# R2P_XXX_module.net
KiCad netlist of a schematic drawn in EAGLE
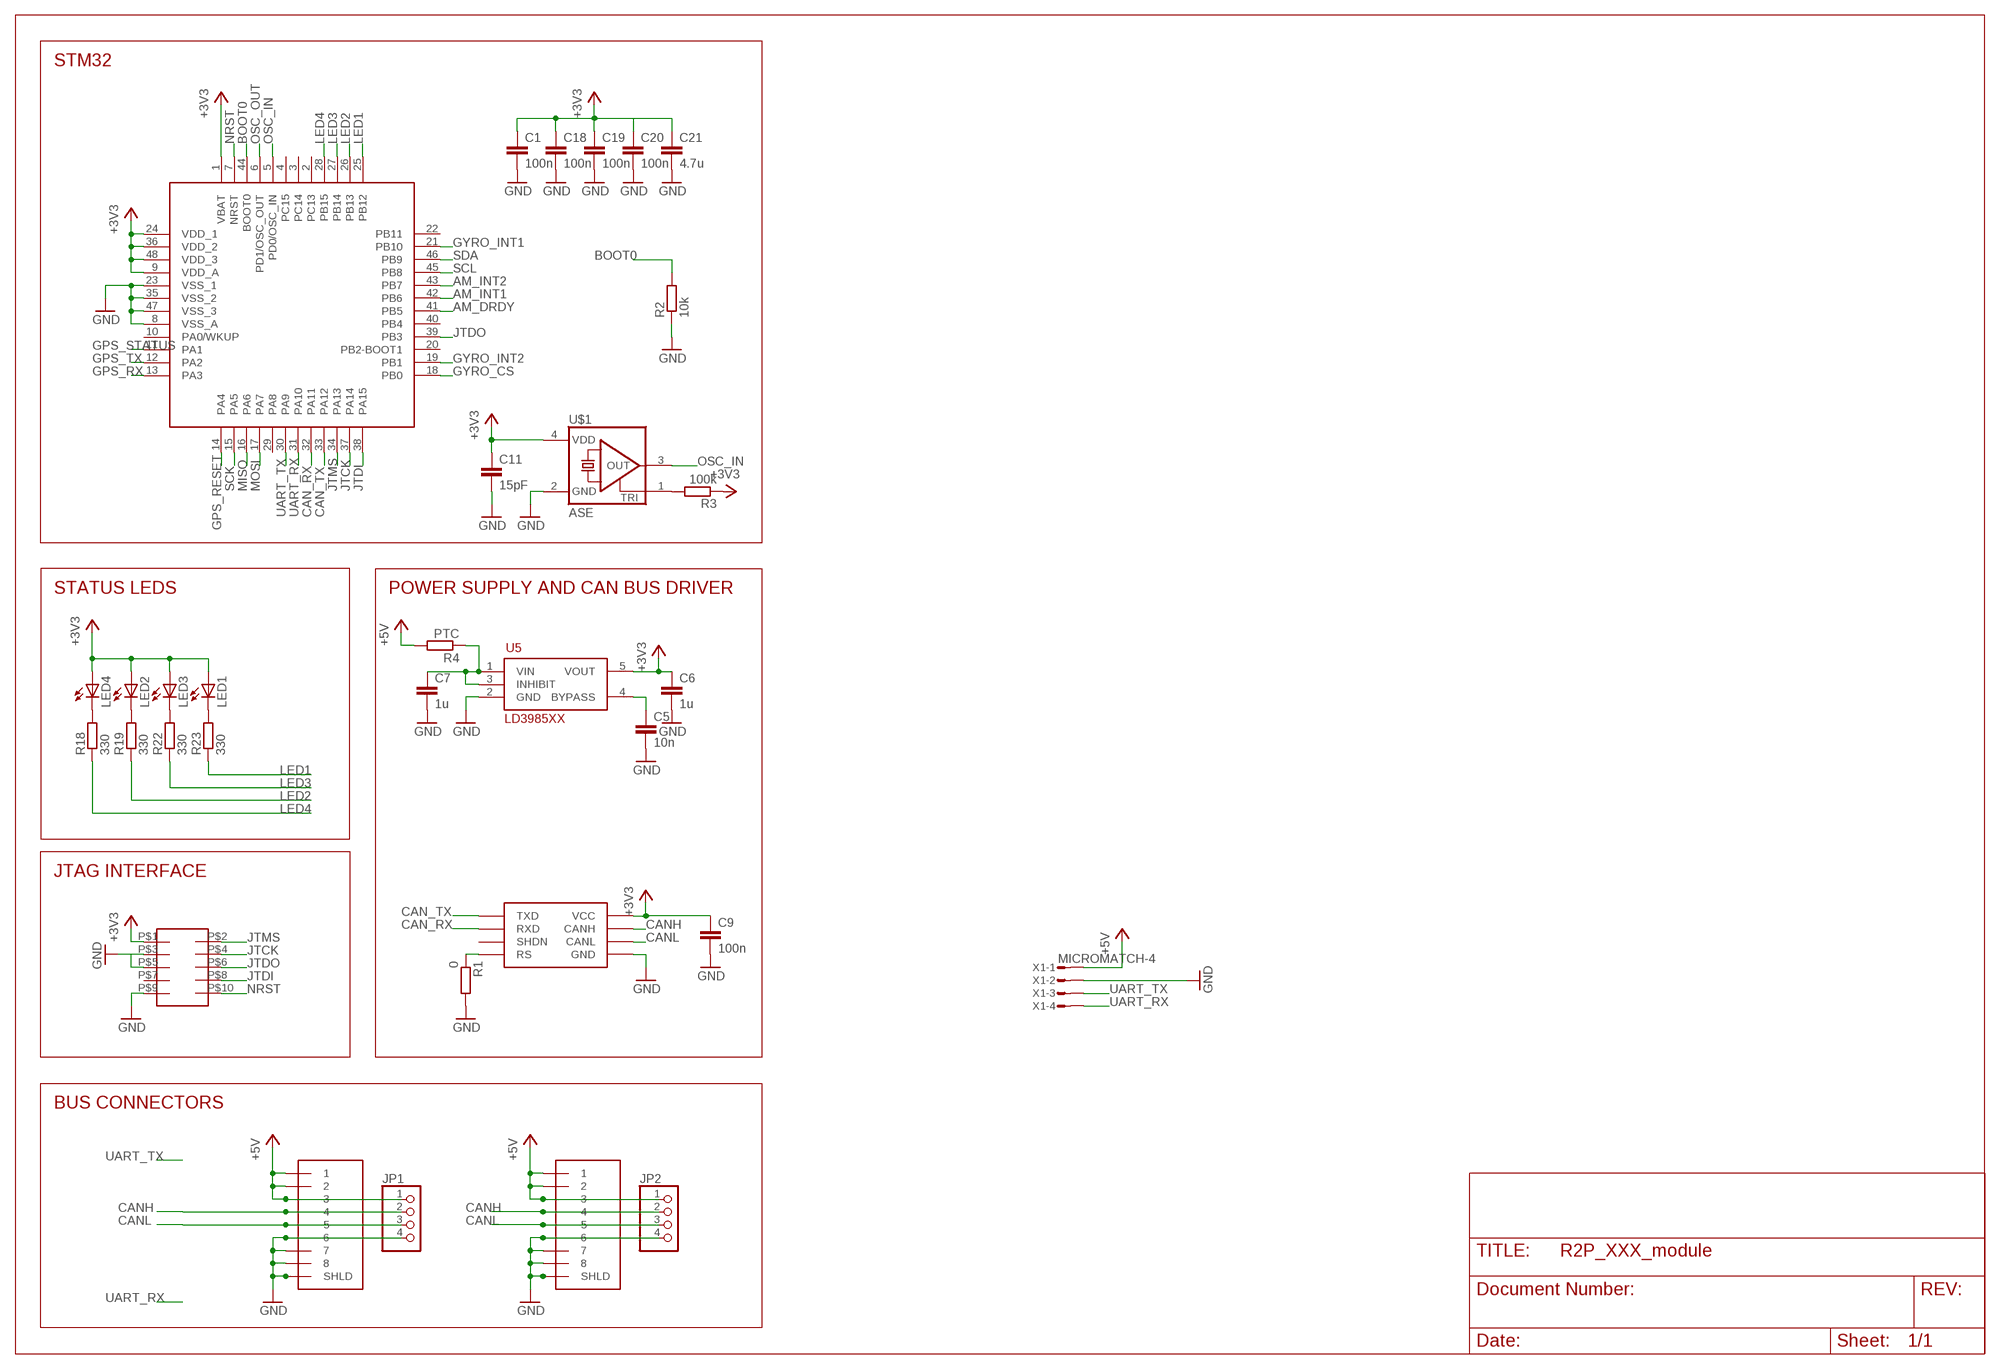
[diagram p0: schematic, sheet 1]

(export (version "E")
  (design (tool "Eeschema 10.0.6"))
  (components
    (comp (ref "1")
      (value "RJ45-43860")
      (footprint "eagle-import:0438600010")
      (libsource (lib "eagle-import") (part "RJ45-43860"))
    )
    (comp (ref "2")
      (value "RJ45-43860")
      (footprint "eagle-import:0438600010")
      (libsource (lib "eagle-import") (part "RJ45-43860"))
    )
    (comp (ref "C1")
      (value "100n")
      (footprint "eagle-import:C0603")
      (libsource (lib "eagle-import") (part "C-EUC0603"))
    )
    (comp (ref "C5")
      (value "10n")
      (footprint "eagle-import:C0603")
      (libsource (lib "eagle-import") (part "C-EUC0603"))
    )
    (comp (ref "C6")
      (value "1u")
      (footprint "eagle-import:C0603")
      (libsource (lib "eagle-import") (part "C-EUC0603"))
    )
    (comp (ref "C7")
      (value "1u")
      (footprint "eagle-import:C0603")
      (libsource (lib "eagle-import") (part "C-EUC0603"))
    )
    (comp (ref "C9")
      (value "100n")
      (footprint "eagle-import:C0603")
      (libsource (lib "eagle-import") (part "C-EUC0603"))
    )
    (comp (ref "C11")
      (value "15pF")
      (footprint "eagle-import:C0603")
      (libsource (lib "eagle-import") (part "C-EUC0603"))
    )
    (comp (ref "C18")
      (value "100n")
      (footprint "eagle-import:C0603")
      (libsource (lib "eagle-import") (part "C-EUC0603"))
    )
    (comp (ref "C19")
      (value "100n")
      (footprint "eagle-import:C0603")
      (libsource (lib "eagle-import") (part "C-EUC0603"))
    )
    (comp (ref "C20")
      (value "100n")
      (footprint "eagle-import:C0603")
      (libsource (lib "eagle-import") (part "C-EUC0603"))
    )
    (comp (ref "C21")
      (value "4.7u")
      (footprint "eagle-import:C0805")
      (libsource (lib "eagle-import") (part "C-EUC0805"))
    )
    (comp (ref "JP1")
      (value "PINHD-1X4")
      (footprint "eagle-import:1X04")
      (libsource (lib "eagle-import") (part "PINHD-1X4"))
    )
    (comp (ref "JP2")
      (value "PINHD-1X4")
      (footprint "eagle-import:1X04")
      (libsource (lib "eagle-import") (part "PINHD-1X4"))
    )
    (comp (ref "LED1")
      (value "LEDCHIPLED_0805")
      (footprint "eagle-import:CHIPLED_0805")
      (libsource (lib "eagle-import") (part "LEDCHIPLED_0805"))
    )
    (comp (ref "LED2")
      (value "LEDCHIPLED_0805")
      (footprint "eagle-import:CHIPLED_0805")
      (libsource (lib "eagle-import") (part "LEDCHIPLED_0805"))
    )
    (comp (ref "LED3")
      (value "LEDCHIPLED_0805")
      (footprint "eagle-import:CHIPLED_0805")
      (libsource (lib "eagle-import") (part "LEDCHIPLED_0805"))
    )
    (comp (ref "LED4")
      (value "LEDCHIPLED_0805")
      (footprint "eagle-import:CHIPLED_0805")
      (libsource (lib "eagle-import") (part "LEDCHIPLED_0805"))
    )
    (comp (ref "R1")
      (value "0")
      (footprint "eagle-import:R0603")
      (libsource (lib "eagle-import") (part "R-EU_R0603"))
    )
    (comp (ref "R2")
      (value "10k")
      (footprint "eagle-import:R0603")
      (libsource (lib "eagle-import") (part "R-EU_R0603"))
    )
    (comp (ref "R3")
      (value "100k")
      (footprint "eagle-import:R0603")
      (libsource (lib "eagle-import") (part "R-EU_R0603"))
    )
    (comp (ref "R4")
      (value "PTC")
      (footprint "eagle-import:R0603")
      (libsource (lib "eagle-import") (part "R-EU_R0603"))
    )
    (comp (ref "R18")
      (value "330")
      (footprint "eagle-import:R0603")
      (libsource (lib "eagle-import") (part "R-EU_R0603"))
    )
    (comp (ref "R19")
      (value "330")
      (footprint "eagle-import:R0603")
      (libsource (lib "eagle-import") (part "R-EU_R0603"))
    )
    (comp (ref "R22")
      (value "330")
      (footprint "eagle-import:R0603")
      (libsource (lib "eagle-import") (part "R-EU_R0603"))
    )
    (comp (ref "R23")
      (value "330")
      (footprint "eagle-import:R0603")
      (libsource (lib "eagle-import") (part "R-EU_R0603"))
    )
    (comp (ref "SOT1")
      (value "MAX3051")
      (footprint "eagle-import:SOT23-8L")
      (libsource (lib "eagle-import") (part "MAX3051"))
    )
    (comp (ref "U$1")
      (value "ASE")
      (footprint "eagle-import:ASE")
      (libsource (lib "eagle-import") (part "ASE"))
    )
    (comp (ref "U$4")
      (value "FTSH-105")
      (footprint "eagle-import:FTSH-105")
      (libsource (lib "eagle-import") (part "FTSH-105"))
    )
    (comp (ref "U1")
      (value "STM32F103CX")
      (footprint "eagle-import:LQFP48")
      (libsource (lib "eagle-import") (part "STM32F103CX"))
    )
    (comp (ref "U5")
      (value "LD3985XX")
      (footprint "eagle-import:SOT23-5L")
      (libsource (lib "eagle-import") (part "LD3985XX"))
    )
    (comp (ref "X1")
      (value "MICROMATCH-4")
      (footprint "eagle-import:MICROMATCH-4")
      (libsource (lib "eagle-import") (part "MICROMATCH-4"))
    )
  )
  (nets
    (net (code "1") (name "+3V3") (class "Default")
      (node (ref "C1") (pin "1") (pinfunction "1_1") (pintype "passive"))
      (node (ref "C11") (pin "1") (pinfunction "1_1") (pintype "passive"))
      (node (ref "C18") (pin "1") (pinfunction "1_1") (pintype "passive"))
      (node (ref "C19") (pin "1") (pinfunction "1_1") (pintype "passive"))
      (node (ref "C20") (pin "1") (pinfunction "1_1") (pintype "passive"))
      (node (ref "C21") (pin "1") (pinfunction "1_1") (pintype "passive"))
      (node (ref "C6") (pin "1") (pinfunction "1_1") (pintype "passive"))
      (node (ref "C9") (pin "1") (pinfunction "1_1") (pintype "passive"))
      (node (ref "LED1") (pin "A") (pinfunction "A_A") (pintype "passive"))
      (node (ref "LED2") (pin "A") (pinfunction "A_A") (pintype "passive"))
      (node (ref "LED3") (pin "A") (pinfunction "A_A") (pintype "passive"))
      (node (ref "LED4") (pin "A") (pinfunction "A_A") (pintype "passive"))
      (node (ref "R3") (pin "1") (pinfunction "1_1") (pintype "passive"))
      (node (ref "SOT1") (pin "P$3") (pinfunction "VCC_P$3") (pintype "bidirectional"))
      (node (ref "U$1") (pin "4") (pinfunction "VDD_4") (pintype "power_in"))
      (node (ref "U$4") (pin "P$1") (pinfunction "P$1_P$1") (pintype "bidirectional"))
      (node (ref "U1") (pin "1") (pinfunction "VBAT_1") (pintype "bidirectional"))
      (node (ref "U1") (pin "24") (pinfunction "VDD_1_24") (pintype "bidirectional"))
      (node (ref "U1") (pin "36") (pinfunction "VDD_2_36") (pintype "bidirectional"))
      (node (ref "U1") (pin "48") (pinfunction "VDD_3_48") (pintype "bidirectional"))
      (node (ref "U1") (pin "9") (pinfunction "VDD_A_9") (pintype "bidirectional"))
      (node (ref "U5") (pin "5") (pinfunction "VOUT_5") (pintype "bidirectional"))
    )
    (net (code "2") (name "+5V") (class "Default")
      (node (ref "1") (pin "P$1") (pinfunction "1_P$1") (pintype "bidirectional"))
      (node (ref "1") (pin "P$2") (pinfunction "2_P$2") (pintype "bidirectional"))
      (node (ref "1") (pin "P$3") (pinfunction "3_P$3") (pintype "bidirectional"))
      (node (ref "2") (pin "P$1") (pinfunction "1_P$1") (pintype "bidirectional"))
      (node (ref "2") (pin "P$2") (pinfunction "2_P$2") (pintype "bidirectional"))
      (node (ref "2") (pin "P$3") (pinfunction "3_P$3") (pintype "bidirectional"))
      (node (ref "JP1") (pin "1") (pinfunction "1_1") (pintype "passive"))
      (node (ref "JP2") (pin "1") (pinfunction "1_1") (pintype "passive"))
      (node (ref "R4") (pin "2") (pinfunction "2_2") (pintype "passive"))
      (node (ref "X1") (pin "1") (pinfunction "S_1") (pintype "passive"))
    )
    (net (code "3") (name "/AM_DRDY") (class "Default")
      (node (ref "U1") (pin "41") (pinfunction "PB5_41") (pintype "bidirectional"))
    )
    (net (code "4") (name "/AM_INT1") (class "Default")
      (node (ref "U1") (pin "42") (pinfunction "PB6_42") (pintype "bidirectional"))
    )
    (net (code "5") (name "/AM_INT2") (class "Default")
      (node (ref "U1") (pin "43") (pinfunction "PB7_43") (pintype "bidirectional"))
    )
    (net (code "6") (name "/BOOT0") (class "Default")
      (node (ref "R2") (pin "2") (pinfunction "2_2") (pintype "passive"))
      (node (ref "U1") (pin "44") (pinfunction "BOOT0_44") (pintype "bidirectional"))
    )
    (net (code "7") (name "/CANH") (class "Default")
      (node (ref "1") (pin "P$4") (pinfunction "4_P$4") (pintype "bidirectional"))
      (node (ref "2") (pin "P$4") (pinfunction "4_P$4") (pintype "bidirectional"))
      (node (ref "JP1") (pin "2") (pinfunction "2_2") (pintype "passive"))
      (node (ref "JP2") (pin "2") (pinfunction "2_2") (pintype "passive"))
      (node (ref "SOT1") (pin "P$7") (pinfunction "CANH_P$7") (pintype "bidirectional"))
    )
    (net (code "8") (name "/CANL") (class "Default")
      (node (ref "1") (pin "P$5") (pinfunction "5_P$5") (pintype "bidirectional"))
      (node (ref "2") (pin "P$5") (pinfunction "5_P$5") (pintype "bidirectional"))
      (node (ref "JP1") (pin "3") (pinfunction "3_3") (pintype "passive"))
      (node (ref "JP2") (pin "3") (pinfunction "3_3") (pintype "passive"))
      (node (ref "SOT1") (pin "P$6") (pinfunction "CANL_P$6") (pintype "bidirectional"))
    )
    (net (code "9") (name "/CAN_RX") (class "Default")
      (node (ref "SOT1") (pin "P$4") (pinfunction "RXD_P$4") (pintype "bidirectional"))
      (node (ref "U1") (pin "32") (pinfunction "PA11_32") (pintype "bidirectional"))
    )
    (net (code "10") (name "/CAN_TX") (class "Default")
      (node (ref "SOT1") (pin "P$1") (pinfunction "TXD_P$1") (pintype "bidirectional"))
      (node (ref "U1") (pin "33") (pinfunction "PA12_33") (pintype "bidirectional"))
    )
    (net (code "11") (name "/GPS_RESET") (class "Default")
      (node (ref "U1") (pin "14") (pinfunction "PA4_14") (pintype "bidirectional"))
    )
    (net (code "12") (name "/GPS_RX") (class "Default")
      (node (ref "U1") (pin "13") (pinfunction "PA3_13") (pintype "bidirectional"))
    )
    (net (code "13") (name "/GPS_STATUS") (class "Default")
      (node (ref "U1") (pin "11") (pinfunction "PA1_11") (pintype "bidirectional"))
    )
    (net (code "14") (name "/GPS_TX") (class "Default")
      (node (ref "U1") (pin "12") (pinfunction "PA2_12") (pintype "bidirectional"))
    )
    (net (code "15") (name "/GYRO_CS") (class "Default")
      (node (ref "U1") (pin "18") (pinfunction "PB0_18") (pintype "bidirectional"))
    )
    (net (code "16") (name "/GYRO_INT1") (class "Default")
      (node (ref "U1") (pin "21") (pinfunction "PB10_21") (pintype "bidirectional"))
    )
    (net (code "17") (name "/GYRO_INT2") (class "Default")
      (node (ref "U1") (pin "19") (pinfunction "PB1_19") (pintype "bidirectional"))
    )
    (net (code "18") (name "/JTCK") (class "Default")
      (node (ref "U$4") (pin "P$4") (pinfunction "P$4_P$4") (pintype "bidirectional"))
      (node (ref "U1") (pin "37") (pinfunction "PA14_37") (pintype "bidirectional"))
    )
    (net (code "19") (name "/JTDI") (class "Default")
      (node (ref "U$4") (pin "P$8") (pinfunction "P$8_P$8") (pintype "bidirectional"))
      (node (ref "U1") (pin "38") (pinfunction "PA15_38") (pintype "bidirectional"))
    )
    (net (code "20") (name "/JTDO") (class "Default")
      (node (ref "U$4") (pin "P$6") (pinfunction "P$6_P$6") (pintype "bidirectional"))
      (node (ref "U1") (pin "39") (pinfunction "PB3_39") (pintype "bidirectional"))
    )
    (net (code "21") (name "/JTMS") (class "Default")
      (node (ref "U$4") (pin "P$2") (pinfunction "P$2_P$2") (pintype "bidirectional"))
      (node (ref "U1") (pin "34") (pinfunction "PA13_34") (pintype "bidirectional"))
    )
    (net (code "22") (name "/LED1") (class "Default")
      (node (ref "R23") (pin "1") (pinfunction "1_1") (pintype "passive"))
      (node (ref "U1") (pin "25") (pinfunction "PB12_25") (pintype "bidirectional"))
    )
    (net (code "23") (name "/LED2") (class "Default")
      (node (ref "R19") (pin "1") (pinfunction "1_1") (pintype "passive"))
      (node (ref "U1") (pin "26") (pinfunction "PB13_26") (pintype "bidirectional"))
    )
    (net (code "24") (name "/LED3") (class "Default")
      (node (ref "R22") (pin "1") (pinfunction "1_1") (pintype "passive"))
      (node (ref "U1") (pin "27") (pinfunction "PB14_27") (pintype "bidirectional"))
    )
    (net (code "25") (name "/LED4") (class "Default")
      (node (ref "R18") (pin "1") (pinfunction "1_1") (pintype "passive"))
      (node (ref "U1") (pin "28") (pinfunction "PB15_28") (pintype "bidirectional"))
    )
    (net (code "26") (name "/MISO") (class "Default")
      (node (ref "U1") (pin "16") (pinfunction "PA6_16") (pintype "bidirectional"))
    )
    (net (code "27") (name "/MOSI") (class "Default")
      (node (ref "U1") (pin "17") (pinfunction "PA7_17") (pintype "bidirectional"))
    )
    (net (code "28") (name "/NRST") (class "Default")
      (node (ref "U$4") (pin "P$10") (pinfunction "P$10_P$10") (pintype "bidirectional"))
      (node (ref "U1") (pin "7") (pinfunction "NRST_7") (pintype "bidirectional"))
    )
    (net (code "29") (name "/OSC_IN") (class "Default")
      (node (ref "U$1") (pin "3") (pinfunction "OUT_3") (pintype "output"))
      (node (ref "U1") (pin "5") (pinfunction "PD0/OSC_IN_5") (pintype "bidirectional"))
    )
    (net (code "30") (name "/OSC_OUT") (class "Default")
      (node (ref "U1") (pin "6") (pinfunction "PD1/OSC_OUT_6") (pintype "bidirectional"))
    )
    (net (code "31") (name "/SCK") (class "Default")
      (node (ref "U1") (pin "15") (pinfunction "PA5_15") (pintype "bidirectional"))
    )
    (net (code "32") (name "/SCL") (class "Default")
      (node (ref "U1") (pin "45") (pinfunction "PB8_45") (pintype "bidirectional"))
    )
    (net (code "33") (name "/SDA") (class "Default")
      (node (ref "U1") (pin "46") (pinfunction "PB9_46") (pintype "bidirectional"))
    )
    (net (code "34") (name "/UART_RX") (class "Default")
      (node (ref "U1") (pin "31") (pinfunction "PA10_31") (pintype "bidirectional"))
      (node (ref "X1") (pin "4") (pinfunction "S_4") (pintype "passive"))
    )
    (net (code "35") (name "/UART_TX") (class "Default")
      (node (ref "U1") (pin "30") (pinfunction "PA9_30") (pintype "bidirectional"))
      (node (ref "X1") (pin "3") (pinfunction "S_3") (pintype "passive"))
    )
    (net (code "36") (name "GND") (class "Default")
      (node (ref "1") (pin "P$10") (pinfunction "P$1_P$10") (pintype "power_in"))
      (node (ref "1") (pin "P$6") (pinfunction "6_P$6") (pintype "bidirectional"))
      (node (ref "1") (pin "P$7") (pinfunction "7_P$7") (pintype "bidirectional"))
      (node (ref "1") (pin "P$8") (pinfunction "8_P$8") (pintype "bidirectional"))
      (node (ref "1") (pin "P$9") (pinfunction "SHLD_P$9") (pintype "power_in"))
      (node (ref "2") (pin "P$10") (pinfunction "P$1_P$10") (pintype "power_in"))
      (node (ref "2") (pin "P$6") (pinfunction "6_P$6") (pintype "bidirectional"))
      (node (ref "2") (pin "P$7") (pinfunction "7_P$7") (pintype "bidirectional"))
      (node (ref "2") (pin "P$8") (pinfunction "8_P$8") (pintype "bidirectional"))
      (node (ref "2") (pin "P$9") (pinfunction "SHLD_P$9") (pintype "power_in"))
      (node (ref "C1") (pin "2") (pinfunction "2_2") (pintype "passive"))
      (node (ref "C11") (pin "2") (pinfunction "2_2") (pintype "passive"))
      (node (ref "C18") (pin "2") (pinfunction "2_2") (pintype "passive"))
      (node (ref "C19") (pin "2") (pinfunction "2_2") (pintype "passive"))
      (node (ref "C20") (pin "2") (pinfunction "2_2") (pintype "passive"))
      (node (ref "C21") (pin "2") (pinfunction "2_2") (pintype "passive"))
      (node (ref "C5") (pin "2") (pinfunction "2_2") (pintype "passive"))
      (node (ref "C6") (pin "2") (pinfunction "2_2") (pintype "passive"))
      (node (ref "C7") (pin "2") (pinfunction "2_2") (pintype "passive"))
      (node (ref "C9") (pin "2") (pinfunction "2_2") (pintype "passive"))
      (node (ref "JP1") (pin "4") (pinfunction "4_4") (pintype "passive"))
      (node (ref "JP2") (pin "4") (pinfunction "4_4") (pintype "passive"))
      (node (ref "R1") (pin "2") (pinfunction "2_2") (pintype "passive"))
      (node (ref "R2") (pin "1") (pinfunction "1_1") (pintype "passive"))
      (node (ref "SOT1") (pin "P$2") (pinfunction "GND_P$2") (pintype "bidirectional"))
      (node (ref "U$1") (pin "2") (pinfunction "GND_2") (pintype "power_in"))
      (node (ref "U$4") (pin "P$3") (pinfunction "P$3_P$3") (pintype "bidirectional"))
      (node (ref "U$4") (pin "P$9") (pinfunction "P$9_P$9") (pintype "bidirectional"))
      (node (ref "U1") (pin "23") (pinfunction "VSS_1_23") (pintype "bidirectional"))
      (node (ref "U1") (pin "35") (pinfunction "VSS_2_35") (pintype "bidirectional"))
      (node (ref "U1") (pin "47") (pinfunction "VSS_3_47") (pintype "bidirectional"))
      (node (ref "U1") (pin "8") (pinfunction "VSS_A_8") (pintype "bidirectional"))
      (node (ref "U5") (pin "2") (pinfunction "GND_2") (pintype "bidirectional"))
      (node (ref "X1") (pin "2") (pinfunction "S_2") (pintype "passive"))
    )
    (net (code "37") (name "Net-(LED1-PadC)") (class "Default")
      (node (ref "LED1") (pin "C") (pinfunction "C_C") (pintype "passive"))
      (node (ref "R23") (pin "2") (pinfunction "2_2") (pintype "passive"))
    )
    (net (code "38") (name "Net-(LED2-PadC)") (class "Default")
      (node (ref "LED2") (pin "C") (pinfunction "C_C") (pintype "passive"))
      (node (ref "R19") (pin "2") (pinfunction "2_2") (pintype "passive"))
    )
    (net (code "39") (name "Net-(LED3-PadC)") (class "Default")
      (node (ref "LED3") (pin "C") (pinfunction "C_C") (pintype "passive"))
      (node (ref "R22") (pin "2") (pinfunction "2_2") (pintype "passive"))
    )
    (net (code "40") (name "Net-(LED4-PadC)") (class "Default")
      (node (ref "LED4") (pin "C") (pinfunction "C_C") (pintype "passive"))
      (node (ref "R18") (pin "2") (pinfunction "2_2") (pintype "passive"))
    )
    (net (code "41") (name "Net-(SOT1-RS)") (class "Default")
      (node (ref "R1") (pin "1") (pinfunction "1_1") (pintype "passive"))
      (node (ref "SOT1") (pin "P$8") (pinfunction "RS_P$8") (pintype "bidirectional"))
    )
    (net (code "42") (name "Net-(U$1-TRI)") (class "Default")
      (node (ref "R3") (pin "2") (pinfunction "2_2") (pintype "passive"))
      (node (ref "U$1") (pin "1") (pinfunction "TRI_1") (pintype "input"))
    )
    (net (code "43") (name "Net-(U5-BYPASS)") (class "Default")
      (node (ref "C5") (pin "1") (pinfunction "1_1") (pintype "passive"))
      (node (ref "U5") (pin "4") (pinfunction "BYPASS_4") (pintype "bidirectional"))
    )
    (net (code "44") (name "Net-(U5-INHIBIT)") (class "Default")
      (node (ref "C7") (pin "1") (pinfunction "1_1") (pintype "passive"))
      (node (ref "R4") (pin "1") (pinfunction "1_1") (pintype "passive"))
      (node (ref "U5") (pin "1") (pinfunction "VIN_1") (pintype "bidirectional"))
      (node (ref "U5") (pin "3") (pinfunction "INHIBIT_3") (pintype "bidirectional"))
    )
    (net (code "45") (name "unconnected-(SOT1-SHDN-PadP$5)") (class "Default")
      (node (ref "SOT1") (pin "P$5") (pinfunction "SHDN_P$5") (pintype "bidirectional"))
    )
    (net (code "46") (name "unconnected-(U$4-PadP$5)") (class "Default")
      (node (ref "U$4") (pin "P$5") (pinfunction "P$5_P$5") (pintype "bidirectional"))
    )
    (net (code "47") (name "unconnected-(U$4-PadP$7)") (class "Default")
      (node (ref "U$4") (pin "P$7") (pinfunction "P$7_P$7") (pintype "bidirectional"))
    )
    (net (code "48") (name "unconnected-(U1-PA0{slash}WKUP-Pad10)") (class "Default")
      (node (ref "U1") (pin "10") (pinfunction "PA0/WKUP_10") (pintype "bidirectional"))
    )
    (net (code "49") (name "unconnected-(U1-PA8-Pad29)") (class "Default")
      (node (ref "U1") (pin "29") (pinfunction "PA8_29") (pintype "bidirectional"))
    )
    (net (code "50") (name "unconnected-(U1-PB2-BOOT1-Pad20)") (class "Default")
      (node (ref "U1") (pin "20") (pinfunction "PB2-BOOT1_20") (pintype "bidirectional"))
    )
    (net (code "51") (name "unconnected-(U1-PB4-Pad40)") (class "Default")
      (node (ref "U1") (pin "40") (pinfunction "PB4_40") (pintype "bidirectional"))
    )
    (net (code "52") (name "unconnected-(U1-PB11-Pad22)") (class "Default")
      (node (ref "U1") (pin "22") (pinfunction "PB11_22") (pintype "bidirectional"))
    )
    (net (code "53") (name "unconnected-(U1-PC13-Pad2)") (class "Default")
      (node (ref "U1") (pin "2") (pinfunction "PC13_2") (pintype "bidirectional"))
    )
    (net (code "54") (name "unconnected-(U1-PC14-Pad3)") (class "Default")
      (node (ref "U1") (pin "3") (pinfunction "PC14_3") (pintype "bidirectional"))
    )
    (net (code "55") (name "unconnected-(U1-PC15-Pad4)") (class "Default")
      (node (ref "U1") (pin "4") (pinfunction "PC15_4") (pintype "bidirectional"))
    )
  )
)
